# STM32L476_MCU.net
KiCad netlist of a schematic drawn in Altium Designer
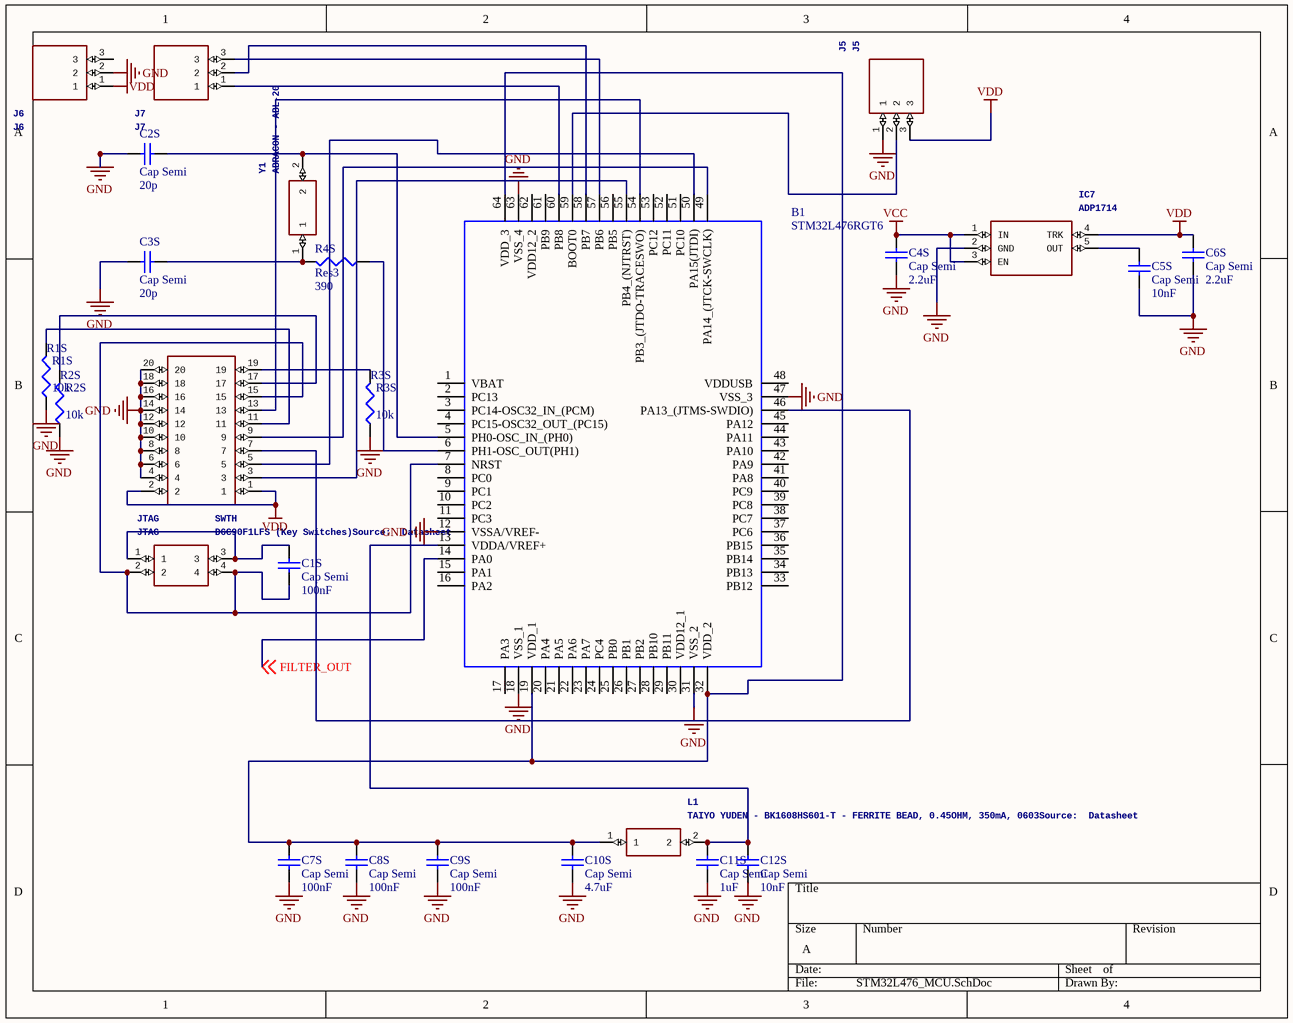
[diagram p0: STM32L476_MCU.SchDoc]

(export (version "E")
  (design (tool "Eeschema 10.0.6"))
  (components
    (comp (ref "B1")
      (value "STM32L476RGT6")
      (footprint "QFP50P1200X1200X160-64N")
      (fields (field (name "RS PART NUMBER") "1658235"))
      (libsource (lib "STM32L476RGT6") (part "STM32L476RGT6"))
    )
    (comp (ref "C1S")
      (value "Cap Semi")
      (footprint "1608[0603]")
      (description "Capacitor (Semiconductor SIM Model)")
      (fields (field (name "ALTIUM_VALUE") "100nF") (field (name "PUBLISHER") "Altium Limited"))
      (libsource (lib "Miscellaneous Devices") (part "Cap Semi"))
    )
    (comp (ref "C2S")
      (value "Cap Semi")
      (footprint "1608[0603]")
      (description "Capacitor (Semiconductor SIM Model)")
      (fields (field (name "ALTIUM_VALUE") "20p") (field (name "PUBLISHER") "Altium Limited"))
      (libsource (lib "Miscellaneous Devices") (part "Cap Semi"))
    )
    (comp (ref "C3S")
      (value "Cap Semi")
      (footprint "1608[0603]")
      (description "Capacitor (Semiconductor SIM Model)")
      (fields (field (name "ALTIUM_VALUE") "20p") (field (name "PUBLISHER") "Altium Limited"))
      (libsource (lib "Miscellaneous Devices") (part "Cap Semi"))
    )
    (comp (ref "C4S")
      (value "Cap Semi")
      (footprint "1608[0603]")
      (description "Capacitor (Semiconductor SIM Model)")
      (fields (field (name "ALTIUM_VALUE") "2.2uF") (field (name "PUBLISHER") "Altium Limited"))
      (libsource (lib "Miscellaneous Devices") (part "Cap Semi"))
    )
    (comp (ref "C5S")
      (value "Cap Semi")
      (footprint "1608[0603]")
      (description "Capacitor (Semiconductor SIM Model)")
      (fields (field (name "ALTIUM_VALUE") "10nF") (field (name "PUBLISHER") "Altium Limited"))
      (libsource (lib "Miscellaneous Devices") (part "Cap Semi"))
    )
    (comp (ref "C6S")
      (value "Cap Semi")
      (footprint "1608[0603]")
      (description "Capacitor (Semiconductor SIM Model)")
      (fields (field (name "ALTIUM_VALUE") "2.2uF") (field (name "PUBLISHER") "Altium Limited"))
      (libsource (lib "Miscellaneous Devices") (part "Cap Semi"))
    )
    (comp (ref "C7S")
      (value "Cap Semi")
      (footprint "1608[0603]")
      (description "Capacitor (Semiconductor SIM Model)")
      (fields (field (name "ALTIUM_VALUE") "100nF") (field (name "PUBLISHER") "Altium Limited"))
      (libsource (lib "Miscellaneous Devices") (part "Cap Semi"))
    )
    (comp (ref "C8S")
      (value "Cap Semi")
      (footprint "1608[0603]")
      (description "Capacitor (Semiconductor SIM Model)")
      (fields (field (name "ALTIUM_VALUE") "100nF") (field (name "PUBLISHER") "Altium Limited"))
      (libsource (lib "Miscellaneous Devices") (part "Cap Semi"))
    )
    (comp (ref "C9S")
      (value "Cap Semi")
      (footprint "1608[0603]")
      (description "Capacitor (Semiconductor SIM Model)")
      (fields (field (name "ALTIUM_VALUE") "100nF") (field (name "PUBLISHER") "Altium Limited"))
      (libsource (lib "Miscellaneous Devices") (part "Cap Semi"))
    )
    (comp (ref "C10S")
      (value "Cap Semi")
      (footprint "1608[0603]")
      (description "Capacitor (Semiconductor SIM Model)")
      (fields (field (name "ALTIUM_VALUE") "4.7uF") (field (name "PUBLISHER") "Altium Limited"))
      (libsource (lib "Miscellaneous Devices") (part "Cap Semi"))
    )
    (comp (ref "C11S")
      (value "Cap Semi")
      (footprint "1608[0603]")
      (description "Capacitor (Semiconductor SIM Model)")
      (fields (field (name "ALTIUM_VALUE") "1uF") (field (name "PUBLISHER") "Altium Limited"))
      (libsource (lib "Miscellaneous Devices") (part "Cap Semi"))
    )
    (comp (ref "C12S")
      (value "Cap Semi")
      (footprint "1608[0603]")
      (description "Capacitor (Semiconductor SIM Model)")
      (fields (field (name "ALTIUM_VALUE") "10nF") (field (name "PUBLISHER") "Altium Limited"))
      (libsource (lib "Miscellaneous Devices") (part "Cap Semi"))
    )
    (comp (ref "IC7")
      (value "ADP1714")
      (footprint "SOT95P280X100-5N")
      (fields (field (name "MANUFACTURER_PART_NUMBER") "ADP1714AUJZ-3.3-R7"))
      (libsource (lib "ADP1714AUJZ-3") (part "ADP1714AUJZ-3.3-R7"))
    )
    (comp (ref "J5")
      (value "J5")
      (footprint "HDRV3W95P0X254_1X3_762X254X869")
      (fields
        (field (name "MANUFACTURER_PART_NUMBER") "61300311121")
        (field (name "RS_PART_NUMBER") "1725145")
      )
      (libsource (lib "61300311121") (part "61300311121"))
    )
    (comp (ref "J6")
      (value "J6")
      (footprint "HDRV3W95P0X254_1X3_762X254X869")
      (fields
        (field (name "MANUFACTURER_PART_NUMBER") "61300311121")
        (field (name "RS_PART_NUMBER") "1725145")
      )
      (libsource (lib "61300311121") (part "61300311121"))
    )
    (comp (ref "J7")
      (value "J7")
      (footprint "HDRV3W95P0X254_1X3_762X254X869")
      (fields
        (field (name "MANUFACTURER_PART_NUMBER") "61300311121")
        (field (name "RS_PART_NUMBER") "1725145")
      )
      (libsource (lib "61300311121") (part "61300311121"))
    )
    (comp (ref "JTAG")
      (value "JTAG")
      (footprint "SAMTEC_SSW-110-01-G")
      (fields
        (field (name "MANUFACTURER_PART_NUMBER") "SSW-110-01-G-D")
        (field (name "RS_PART_NUMBER") "7655727P")
      )
      (libsource (lib "SSW-110-01-G-D") (part "SSW-110-01-G-D"))
    )
    (comp (ref "L1")
      (value "TAIYO YUDEN - BK1608HS601-T - FERRITE BEAD, 0.45OHM, 350mA, 0603Source:  Datasheet")
      (footprint "BEADC1608X95N")
      (fields (field (name "MANUFACTURER_PART_NUMBER") "BK1608HS601-T"))
      (libsource (lib "BK1608HS601-T") (part "BK1608HS601-T"))
    )
    (comp (ref "R1S")
      (value "R1S")
      (footprint "1608[0603]")
      (description "Resistor")
      (fields (field (name "ALTIUM_VALUE") "10k") (field (name "PUBLISHER") "Altium Limited"))
      (libsource (lib "Miscellaneous Devices") (part "Res3"))
    )
    (comp (ref "R2S")
      (value "R2S")
      (footprint "1608[0603]")
      (description "Resistor")
      (fields (field (name "ALTIUM_VALUE") "10k") (field (name "PUBLISHER") "Altium Limited"))
      (libsource (lib "Miscellaneous Devices") (part "Res3"))
    )
    (comp (ref "R3S")
      (value "R3S")
      (footprint "1608[0603]")
      (description "Resistor")
      (fields (field (name "ALTIUM_VALUE") "10k") (field (name "PUBLISHER") "Altium Limited"))
      (libsource (lib "Miscellaneous Devices") (part "Res3"))
    )
    (comp (ref "R4S")
      (value "Res3")
      (footprint "1608[0603]")
      (description "Resistor")
      (fields (field (name "ALTIUM_VALUE") "390") (field (name "PUBLISHER") "Altium Limited"))
      (libsource (lib "Miscellaneous Devices") (part "Res3"))
    )
    (comp (ref "SWTH")
      (value "D6C90F1LFS (Key Switches)Source:  Datasheet")
      (footprint "D6C10F1LFS")
      (fields (field (name "MANUFACTURER_PART_NUMBER") "D6C90F1LFS"))
      (libsource (lib "D6C90F1LFS") (part "D6C90F1LFS"))
    )
    (comp (ref "Y1")
      (value "ABRACON - ABL-20")
      (footprint "HC/49US_(AT49)PTH")
      (fields
        (field (name "MANUFACTURER_PART_NUMBER") "ABL-20.000MHZ-B2")
        (field (name "RS_PART_NUMBER") "1710202")
      )
      (libsource (lib "ABL-20") (part "ABL-20.000MHZ-B2"))
    )
  )
  (nets
    (net (code "1") (name "FILTER_OUT") (class "Default")
      (node (ref "B1") (pin "14") (pinfunction "PA0_14") (pintype "passive"))
    )
    (net (code "2") (name "GND") (class "Default")
      (node (ref "B1") (pin "12") (pinfunction "VSSA/VREF-_12") (pintype "passive"))
      (node (ref "B1") (pin "18") (pinfunction "VSS_1_18") (pintype "passive"))
      (node (ref "B1") (pin "31") (pinfunction "VSS_2_31") (pintype "passive"))
      (node (ref "B1") (pin "47") (pinfunction "VSS_3_47") (pintype "passive"))
      (node (ref "B1") (pin "63") (pinfunction "VSS_4_63") (pintype "passive"))
      (node (ref "C10S") (pin "1") (pinfunction "1_1") (pintype "passive"))
      (node (ref "C11S") (pin "1") (pinfunction "1_1") (pintype "passive"))
      (node (ref "C12S") (pin "1") (pinfunction "1_1") (pintype "passive"))
      (node (ref "C2S") (pin "1") (pinfunction "1_1") (pintype "passive"))
      (node (ref "C3S") (pin "1") (pinfunction "1_1") (pintype "passive"))
      (node (ref "C4S") (pin "1") (pinfunction "1_1") (pintype "passive"))
      (node (ref "C5S") (pin "1") (pinfunction "1_1") (pintype "passive"))
      (node (ref "C6S") (pin "1") (pinfunction "1_1") (pintype "passive"))
      (node (ref "C7S") (pin "1") (pinfunction "1_1") (pintype "passive"))
      (node (ref "C8S") (pin "1") (pinfunction "1_1") (pintype "passive"))
      (node (ref "C9S") (pin "1") (pinfunction "1_1") (pintype "passive"))
      (node (ref "IC7") (pin "2") (pinfunction "GND_2") (pintype "bidirectional"))
      (node (ref "J5") (pin "1") (pinfunction "1_1") (pintype "bidirectional"))
      (node (ref "J6") (pin "2") (pinfunction "2_2") (pintype "bidirectional"))
      (node (ref "JTAG") (pin "10") (pinfunction "10_10") (pintype "bidirectional"))
      (node (ref "JTAG") (pin "12") (pinfunction "12_12") (pintype "bidirectional"))
      (node (ref "JTAG") (pin "14") (pinfunction "14_14") (pintype "bidirectional"))
      (node (ref "JTAG") (pin "16") (pinfunction "16_16") (pintype "bidirectional"))
      (node (ref "JTAG") (pin "18") (pinfunction "18_18") (pintype "bidirectional"))
      (node (ref "JTAG") (pin "20") (pinfunction "20_20") (pintype "bidirectional"))
      (node (ref "JTAG") (pin "4") (pinfunction "4_4") (pintype "bidirectional"))
      (node (ref "JTAG") (pin "6") (pinfunction "6_6") (pintype "bidirectional"))
      (node (ref "JTAG") (pin "8") (pinfunction "8_8") (pintype "bidirectional"))
      (node (ref "R1S") (pin "2") (pinfunction "2_2") (pintype "passive"))
      (node (ref "R2S") (pin "2") (pinfunction "2_2") (pintype "passive"))
      (node (ref "R3S") (pin "2") (pinfunction "2_2") (pintype "passive"))
    )
    (net (code "3") (name "Net-(B1-BOOT0)") (class "Default")
      (node (ref "B1") (pin "59") (pinfunction "BOOT0_59") (pintype "passive"))
      (node (ref "J5") (pin "2") (pinfunction "2_2") (pintype "bidirectional"))
    )
    (net (code "4") (name "Net-(B1-NRST)") (class "Default")
      (node (ref "B1") (pin "7") (pinfunction "NRST_7") (pintype "passive"))
      (node (ref "C1S") (pin "2") (pinfunction "2_2") (pintype "passive"))
      (node (ref "JTAG") (pin "15") (pinfunction "15_15") (pintype "bidirectional"))
      (node (ref "SWTH") (pin "2") (pinfunction "2_2") (pintype "bidirectional"))
      (node (ref "SWTH") (pin "4") (pinfunction "4_4") (pintype "bidirectional"))
    )
    (net (code "5") (name "Net-(B1-PA13_(JTMS-SWDIO))") (class "Default")
      (node (ref "B1") (pin "46") (pinfunction "PA13_(JTMS-SWDIO)_46") (pintype "passive"))
      (node (ref "JTAG") (pin "7") (pinfunction "7_7") (pintype "bidirectional"))
    )
    (net (code "6") (name "Net-(B1-PA14_(JTCK-SWCLK))") (class "Default")
      (node (ref "B1") (pin "49") (pinfunction "PA14_(JTCK-SWCLK)_49") (pintype "passive"))
      (node (ref "JTAG") (pin "9") (pinfunction "9_9") (pintype "bidirectional"))
    )
    (net (code "7") (name "Net-(B1-PA15(JTDI))") (class "Default")
      (node (ref "B1") (pin "50") (pinfunction "PA15(JTDI)_50") (pintype "passive"))
      (node (ref "JTAG") (pin "5") (pinfunction "5_5") (pintype "bidirectional"))
    )
    (net (code "8") (name "Net-(B1-PB3_(JTDO-TRACESWO))") (class "Default")
      (node (ref "B1") (pin "54") (pinfunction "PB3_(JTDO-TRACESWO)_54") (pintype "passive"))
      (node (ref "JTAG") (pin "13") (pinfunction "13_13") (pintype "bidirectional"))
    )
    (net (code "9") (name "Net-(B1-PB4_(NJTRST))") (class "Default")
      (node (ref "B1") (pin "55") (pinfunction "PB4_(NJTRST)_55") (pintype "passive"))
      (node (ref "JTAG") (pin "3") (pinfunction "3_3") (pintype "bidirectional"))
    )
    (net (code "10") (name "Net-(B1-PB6)") (class "Default")
      (node (ref "B1") (pin "57") (pinfunction "PB6_57") (pintype "passive"))
      (node (ref "J7") (pin "3") (pinfunction "3_3") (pintype "bidirectional"))
    )
    (net (code "11") (name "Net-(B1-PB7)") (class "Default")
      (node (ref "B1") (pin "58") (pinfunction "PB7_58") (pintype "passive"))
      (node (ref "J7") (pin "2") (pinfunction "2_2") (pintype "bidirectional"))
    )
    (net (code "12") (name "Net-(B1-PB8)") (class "Default")
      (node (ref "B1") (pin "60") (pinfunction "PB8_60") (pintype "passive"))
      (node (ref "J7") (pin "1") (pinfunction "1_1") (pintype "bidirectional"))
    )
    (net (code "13") (name "Net-(B1-PH0-OSC_IN_(PH0))") (class "Default")
      (node (ref "B1") (pin "5") (pinfunction "PH0-OSC_IN_(PH0)_5") (pintype "passive"))
      (node (ref "C2S") (pin "2") (pinfunction "2_2") (pintype "passive"))
      (node (ref "Y1") (pin "2") (pinfunction "2_2") (pintype "bidirectional"))
    )
    (net (code "14") (name "Net-(B1-PH1-OSC_OUT(PH1))") (class "Default")
      (node (ref "B1") (pin "6") (pinfunction "PH1-OSC_OUT(PH1)_6") (pintype "passive"))
      (node (ref "R4S") (pin "2") (pinfunction "2_2") (pintype "passive"))
    )
    (net (code "15") (name "Net-(B1-VDDA{slash}VREF+)") (class "Default")
      (node (ref "B1") (pin "13") (pinfunction "VDDA/VREF+_13") (pintype "passive"))
      (node (ref "C11S") (pin "2") (pinfunction "2_2") (pintype "passive"))
      (node (ref "C12S") (pin "2") (pinfunction "2_2") (pintype "passive"))
      (node (ref "L1") (pin "2") (pinfunction "2_2") (pintype "bidirectional"))
    )
    (net (code "16") (name "Net-(B1-VDD_1)") (class "Default")
      (node (ref "B1") (pin "19") (pinfunction "VDD_1_19") (pintype "passive"))
      (node (ref "B1") (pin "32") (pinfunction "VDD_2_32") (pintype "passive"))
      (node (ref "B1") (pin "64") (pinfunction "VDD_3_64") (pintype "passive"))
      (node (ref "C10S") (pin "2") (pinfunction "2_2") (pintype "passive"))
      (node (ref "C7S") (pin "2") (pinfunction "2_2") (pintype "passive"))
      (node (ref "C8S") (pin "2") (pinfunction "2_2") (pintype "passive"))
      (node (ref "C9S") (pin "2") (pinfunction "2_2") (pintype "passive"))
      (node (ref "L1") (pin "1") (pinfunction "1_1") (pintype "bidirectional"))
    )
    (net (code "17") (name "Net-(C1S-Pad1)") (class "Default")
      (node (ref "C1S") (pin "1") (pinfunction "1_1") (pintype "passive"))
      (node (ref "SWTH") (pin "1") (pinfunction "1_1") (pintype "bidirectional"))
      (node (ref "SWTH") (pin "3") (pinfunction "3_3") (pintype "bidirectional"))
    )
    (net (code "18") (name "Net-(C3S-Pad2)") (class "Default")
      (node (ref "C3S") (pin "2") (pinfunction "2_2") (pintype "passive"))
      (node (ref "R4S") (pin "1") (pinfunction "1_1") (pintype "passive"))
      (node (ref "Y1") (pin "1") (pinfunction "1_1") (pintype "bidirectional"))
    )
    (net (code "19") (name "Net-(IC7-OUT)") (class "Default")
      (node (ref "C5S") (pin "2") (pinfunction "2_2") (pintype "passive"))
      (node (ref "IC7") (pin "5") (pinfunction "OUT_5") (pintype "bidirectional"))
    )
    (net (code "20") (name "Net-(JTAG-Pad11)") (class "Default")
      (node (ref "JTAG") (pin "11") (pinfunction "11_11") (pintype "bidirectional"))
      (node (ref "R1S") (pin "1") (pinfunction "1_1") (pintype "passive"))
    )
    (net (code "21") (name "Net-(JTAG-Pad17)") (class "Default")
      (node (ref "JTAG") (pin "17") (pinfunction "17_17") (pintype "bidirectional"))
      (node (ref "R2S") (pin "1") (pinfunction "1_1") (pintype "passive"))
    )
    (net (code "22") (name "Net-(JTAG-Pad19)") (class "Default")
      (node (ref "JTAG") (pin "19") (pinfunction "19_19") (pintype "bidirectional"))
      (node (ref "R3S") (pin "1") (pinfunction "1_1") (pintype "passive"))
    )
    (net (code "23") (name "VCC") (class "Default")
      (node (ref "C4S") (pin "2") (pinfunction "2_2") (pintype "passive"))
      (node (ref "IC7") (pin "1") (pinfunction "IN_1") (pintype "bidirectional"))
      (node (ref "IC7") (pin "3") (pinfunction "EN_3") (pintype "bidirectional"))
    )
    (net (code "24") (name "VDD") (class "Default")
      (node (ref "C6S") (pin "2") (pinfunction "2_2") (pintype "passive"))
      (node (ref "IC7") (pin "4") (pinfunction "TRK_4") (pintype "bidirectional"))
      (node (ref "J5") (pin "3") (pinfunction "3_3") (pintype "bidirectional"))
      (node (ref "J6") (pin "1") (pinfunction "1_1") (pintype "bidirectional"))
      (node (ref "JTAG") (pin "1") (pinfunction "1_1") (pintype "bidirectional"))
      (node (ref "JTAG") (pin "2") (pinfunction "2_2") (pintype "bidirectional"))
    )
    (net (code "25") (name "unconnected-(B1-PA1-Pad15)") (class "Default")
      (node (ref "B1") (pin "15") (pinfunction "PA1_15") (pintype "passive"))
    )
    (net (code "26") (name "unconnected-(B1-PA2-Pad16)") (class "Default")
      (node (ref "B1") (pin "16") (pinfunction "PA2_16") (pintype "passive"))
    )
    (net (code "27") (name "unconnected-(B1-PA3-Pad17)") (class "Default")
      (node (ref "B1") (pin "17") (pinfunction "PA3_17") (pintype "passive"))
    )
    (net (code "28") (name "unconnected-(B1-PA4-Pad20)") (class "Default")
      (node (ref "B1") (pin "20") (pinfunction "PA4_20") (pintype "passive"))
    )
    (net (code "29") (name "unconnected-(B1-PA5-Pad21)") (class "Default")
      (node (ref "B1") (pin "21") (pinfunction "PA5_21") (pintype "passive"))
    )
    (net (code "30") (name "unconnected-(B1-PA6-Pad22)") (class "Default")
      (node (ref "B1") (pin "22") (pinfunction "PA6_22") (pintype "passive"))
    )
    (net (code "31") (name "unconnected-(B1-PA7-Pad23)") (class "Default")
      (node (ref "B1") (pin "23") (pinfunction "PA7_23") (pintype "passive"))
    )
    (net (code "32") (name "unconnected-(B1-PA8-Pad41)") (class "Default")
      (node (ref "B1") (pin "41") (pinfunction "PA8_41") (pintype "passive"))
    )
    (net (code "33") (name "unconnected-(B1-PA9-Pad42)") (class "Default")
      (node (ref "B1") (pin "42") (pinfunction "PA9_42") (pintype "passive"))
    )
    (net (code "34") (name "unconnected-(B1-PA10-Pad43)") (class "Default")
      (node (ref "B1") (pin "43") (pinfunction "PA10_43") (pintype "passive"))
    )
    (net (code "35") (name "unconnected-(B1-PA11-Pad44)") (class "Default")
      (node (ref "B1") (pin "44") (pinfunction "PA11_44") (pintype "passive"))
    )
    (net (code "36") (name "unconnected-(B1-PA12-Pad45)") (class "Default")
      (node (ref "B1") (pin "45") (pinfunction "PA12_45") (pintype "passive"))
    )
    (net (code "37") (name "unconnected-(B1-PB0-Pad25)") (class "Default")
      (node (ref "B1") (pin "25") (pinfunction "PB0_25") (pintype "passive"))
    )
    (net (code "38") (name "unconnected-(B1-PB1-Pad26)") (class "Default")
      (node (ref "B1") (pin "26") (pinfunction "PB1_26") (pintype "passive"))
    )
    (net (code "39") (name "unconnected-(B1-PB2-Pad27)") (class "Default")
      (node (ref "B1") (pin "27") (pinfunction "PB2_27") (pintype "passive"))
    )
    (net (code "40") (name "unconnected-(B1-PB5-Pad56)") (class "Default")
      (node (ref "B1") (pin "56") (pinfunction "PB5_56") (pintype "passive"))
    )
    (net (code "41") (name "unconnected-(B1-PB9-Pad61)") (class "Default")
      (node (ref "B1") (pin "61") (pinfunction "PB9_61") (pintype "passive"))
    )
    (net (code "42") (name "unconnected-(B1-PB10-Pad28)") (class "Default")
      (node (ref "B1") (pin "28") (pinfunction "PB10_28") (pintype "passive"))
    )
    (net (code "43") (name "unconnected-(B1-PB11-Pad29)") (class "Default")
      (node (ref "B1") (pin "29") (pinfunction "PB11_29") (pintype "passive"))
    )
    (net (code "44") (name "unconnected-(B1-PB12-Pad33)") (class "Default")
      (node (ref "B1") (pin "33") (pinfunction "PB12_33") (pintype "passive"))
    )
    (net (code "45") (name "unconnected-(B1-PB13-Pad34)") (class "Default")
      (node (ref "B1") (pin "34") (pinfunction "PB13_34") (pintype "passive"))
    )
    (net (code "46") (name "unconnected-(B1-PB14-Pad35)") (class "Default")
      (node (ref "B1") (pin "35") (pinfunction "PB14_35") (pintype "passive"))
    )
    (net (code "47") (name "unconnected-(B1-PB15-Pad36)") (class "Default")
      (node (ref "B1") (pin "36") (pinfunction "PB15_36") (pintype "passive"))
    )
    (net (code "48") (name "unconnected-(B1-PC0-Pad8)") (class "Default")
      (node (ref "B1") (pin "8") (pinfunction "PC0_8") (pintype "passive"))
    )
    (net (code "49") (name "unconnected-(B1-PC1-Pad9)") (class "Default")
      (node (ref "B1") (pin "9") (pinfunction "PC1_9") (pintype "passive"))
    )
    (net (code "50") (name "unconnected-(B1-PC2-Pad10)") (class "Default")
      (node (ref "B1") (pin "10") (pinfunction "PC2_10") (pintype "passive"))
    )
    (net (code "51") (name "unconnected-(B1-PC3-Pad11)") (class "Default")
      (node (ref "B1") (pin "11") (pinfunction "PC3_11") (pintype "passive"))
    )
    (net (code "52") (name "unconnected-(B1-PC4-Pad24)") (class "Default")
      (node (ref "B1") (pin "24") (pinfunction "PC4_24") (pintype "passive"))
    )
    (net (code "53") (name "unconnected-(B1-PC6-Pad37)") (class "Default")
      (node (ref "B1") (pin "37") (pinfunction "PC6_37") (pintype "passive"))
    )
    (net (code "54") (name "unconnected-(B1-PC7-Pad38)") (class "Default")
      (node (ref "B1") (pin "38") (pinfunction "PC7_38") (pintype "passive"))
    )
    (net (code "55") (name "unconnected-(B1-PC8-Pad39)") (class "Default")
      (node (ref "B1") (pin "39") (pinfunction "PC8_39") (pintype "passive"))
    )
    (net (code "56") (name "unconnected-(B1-PC9-Pad40)") (class "Default")
      (node (ref "B1") (pin "40") (pinfunction "PC9_40") (pintype "passive"))
    )
    (net (code "57") (name "unconnected-(B1-PC10-Pad51)") (class "Default")
      (node (ref "B1") (pin "51") (pinfunction "PC10_51") (pintype "passive"))
    )
    (net (code "58") (name "unconnected-(B1-PC11-Pad52)") (class "Default")
      (node (ref "B1") (pin "52") (pinfunction "PC11_52") (pintype "passive"))
    )
    (net (code "59") (name "unconnected-(B1-PC12-Pad53)") (class "Default")
      (node (ref "B1") (pin "53") (pinfunction "PC12_53") (pintype "passive"))
    )
    (net (code "60") (name "unconnected-(B1-PC13-Pad2)") (class "Default")
      (node (ref "B1") (pin "2") (pinfunction "PC13_2") (pintype "passive"))
    )
    (net (code "61") (name "unconnected-(B1-PC14-OSC32_IN_(PCM)-Pad3)") (class "Default")
      (node (ref "B1") (pin "3") (pinfunction "PC14-OSC32_IN_(PCM)_3") (pintype "passive"))
    )
    (net (code "62") (name "unconnected-(B1-PC15-OSC32_OUT_(PC15)-Pad4)") (class "Default")
      (node (ref "B1") (pin "4") (pinfunction "PC15-OSC32_OUT_(PC15)_4") (pintype "passive"))
    )
    (net (code "63") (name "unconnected-(B1-VBAT-Pad1)") (class "Default")
      (node (ref "B1") (pin "1") (pinfunction "VBAT_1") (pintype "passive"))
    )
    (net (code "64") (name "unconnected-(B1-VDD12_1-Pad30)") (class "Default")
      (node (ref "B1") (pin "30") (pinfunction "VDD12_1_30") (pintype "passive"))
    )
    (net (code "65") (name "unconnected-(B1-VDD12_2-Pad62)") (class "Default")
      (node (ref "B1") (pin "62") (pinfunction "VDD12_2_62") (pintype "passive"))
    )
    (net (code "66") (name "unconnected-(B1-VDDUSB-Pad48)") (class "Default")
      (node (ref "B1") (pin "48") (pinfunction "VDDUSB_48") (pintype "passive"))
    )
    (net (code "67") (name "unconnected-(J6-Pad3)") (class "Default")
      (node (ref "J6") (pin "3") (pinfunction "3_3") (pintype "bidirectional"))
    )
  )
)
